# ProDoc___2025-04-08.net
KiCad netlist of a schematic drawn in EasyEDA Pro
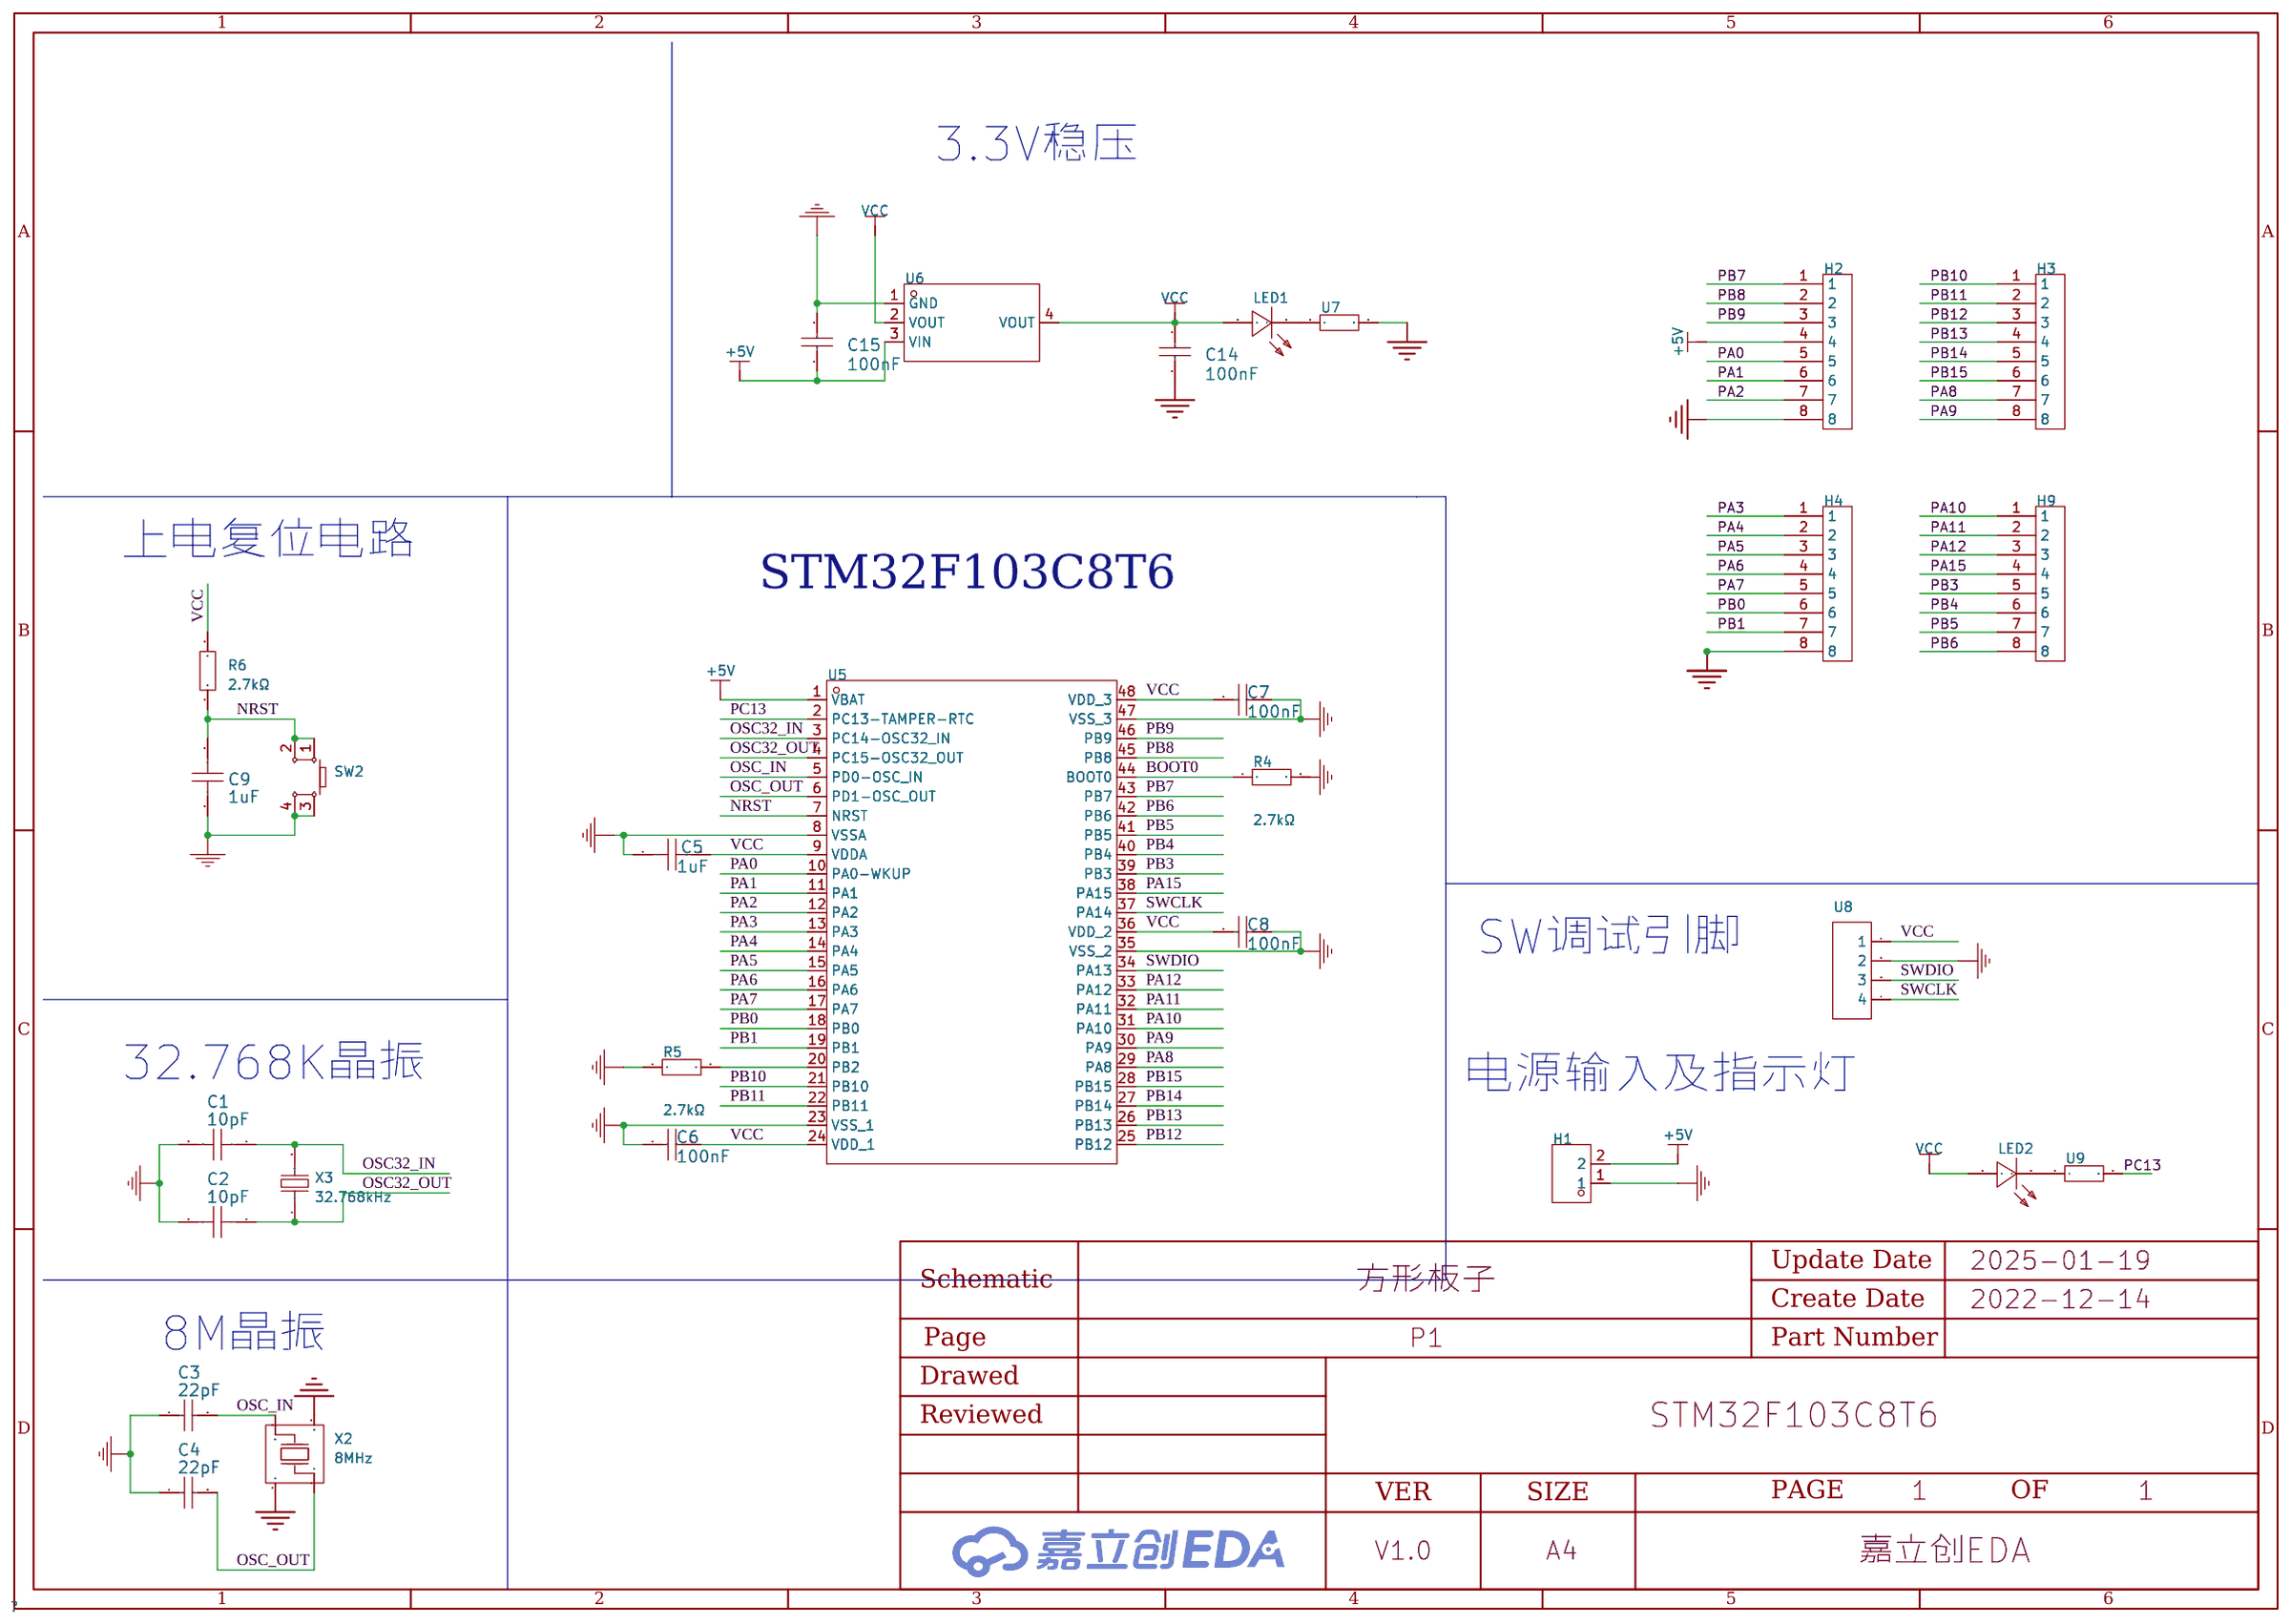
[diagram p0: schematic sheet]

(export (version "E")
  (design (tool "Eeschema 10.0.6"))
  (components
    (comp (ref "C1")
      (value "10pF")
      (footprint "easyedapro:C0603")
      (fields
        (field (name "Manufacturer Part") "CL10C100JB81PNC")
        (field (name "Manufacturer") "Samsung Electro-Mechanics")
      )
      (libsource (lib "easyedapro") (part "10pF"))
    )
    (comp (ref "C2")
      (value "10pF")
      (footprint "easyedapro:C0603")
      (fields
        (field (name "Manufacturer Part") "CL10C100JB81PNC")
        (field (name "Manufacturer") "Samsung Electro-Mechanics")
      )
      (libsource (lib "easyedapro") (part "10pF"))
    )
    (comp (ref "C3")
      (value "22pF")
      (footprint "easyedapro:C0603")
      (fields (field (name "Manufacturer Part") "CL10C220JB8NNNC") (field (name "Manufacturer") "SAMSUNG"))
      (libsource (lib "easyedapro") (part "22pF"))
    )
    (comp (ref "C4")
      (value "22pF")
      (footprint "easyedapro:C0603")
      (fields (field (name "Manufacturer Part") "CL10C220JB8NNNC") (field (name "Manufacturer") "SAMSUNG"))
      (libsource (lib "easyedapro") (part "22pF"))
    )
    (comp (ref "C5")
      (value "1uF")
      (footprint "easyedapro:C0603")
      (fields (field (name "Manufacturer Part") "C0603X5R105K250NT") (field (name "Manufacturer") "SANYEAR"))
      (libsource (lib "easyedapro") (part "1uF"))
    )
    (comp (ref "C6")
      (value "100nF")
      (footprint "easyedapro:C0603")
      (fields (field (name "Manufacturer Part") "0603B104K160") (field (name "Manufacturer") "WTC"))
      (libsource (lib "easyedapro") (part "100nF"))
    )
    (comp (ref "C7")
      (value "100nF")
      (footprint "easyedapro:C0603")
      (fields (field (name "Manufacturer Part") "0603B104K160") (field (name "Manufacturer") "WTC"))
      (libsource (lib "easyedapro") (part "100nF"))
    )
    (comp (ref "C8")
      (value "100nF")
      (footprint "easyedapro:C0603")
      (fields (field (name "Manufacturer Part") "0603B104K160") (field (name "Manufacturer") "WTC"))
      (libsource (lib "easyedapro") (part "100nF"))
    )
    (comp (ref "C9")
      (value "1uF")
      (footprint "easyedapro:C0603")
      (fields (field (name "Manufacturer Part") "C0603X5R105K250NT") (field (name "Manufacturer") "SANYEAR"))
      (libsource (lib "easyedapro") (part "1uF"))
    )
    (comp (ref "C14")
      (value "100nF")
      (footprint "easyedapro:C0603")
      (fields (field (name "Manufacturer Part") "0603B104K160") (field (name "Manufacturer") "WTC"))
      (libsource (lib "easyedapro") (part "100nF"))
    )
    (comp (ref "C15")
      (value "100nF")
      (footprint "easyedapro:C0603")
      (fields (field (name "Manufacturer Part") "0603B104K160") (field (name "Manufacturer") "WTC"))
      (libsource (lib "easyedapro") (part "100nF"))
    )
    (comp (ref "H1")
      (value "PZ254V-11-02P")
      (footprint "easyedapro:HDR-TH_2P-P2.54-V-M")
      (fields (field (name "Manufacturer") "XFCN(兴飞)"))
      (libsource (lib "easyedapro") (part "PZ254V-11-02P"))
    )
    (comp (ref "H2")
      (value "~")
      (footprint "easyedapro:排针8P-直针")
      (libsource (lib "easyedapro") (part "排针8P"))
    )
    (comp (ref "H3")
      (value "~")
      (footprint "easyedapro:排针8P-直针")
      (libsource (lib "easyedapro") (part "排针8P"))
    )
    (comp (ref "H4")
      (value "~")
      (footprint "easyedapro:排针8P-直针")
      (libsource (lib "easyedapro") (part "排针8P"))
    )
    (comp (ref "H9")
      (value "~")
      (footprint "easyedapro:排针8P-直针")
      (libsource (lib "easyedapro") (part "排针8P"))
    )
    (comp (ref "LED1")
      (value "KT-0603R")
      (footprint "easyedapro:LED0603-RD")
      (description "发光颜色:红色;功率:-;正向电流:-;主波长:-;二极管配置:-;透镜颜色:-;色温:-;发光角度:-;载带方式:-;工作温度:-40°C~+85°C;")
      (fields (field (name "Manufacturer") "KENTO"))
      (libsource (lib "easyedapro") (part "KT-0603R"))
    )
    (comp (ref "LED2")
      (value "KT-0603R")
      (footprint "easyedapro:LED0603-RD")
      (description "发光颜色:红色;功率:-;正向电流:-;主波长:-;二极管配置:-;透镜颜色:-;色温:-;发光角度:-;载带方式:-;工作温度:-40°C~+85°C;")
      (fields (field (name "Manufacturer") "KENTO"))
      (libsource (lib "easyedapro") (part "KT-0603R"))
    )
    (comp (ref "R4")
      (value "2.7kΩ")
      (footprint "easyedapro:R0603")
      (description "电阻类型:厚膜电阻;阻值:2.7kΩ;精度:±1%;功率:100mW;温度系数:±100ppm/°C;最大工作电压:75V;工作温度范围:-55°C~+155°C;")
      (fields
        (field (name "Manufacturer Part") "0603WAF2701T5E")
        (field (name "Manufacturer") "UNI-ROYAL(厚声)")
      )
      (libsource (lib "easyedapro") (part "电阻0603"))
    )
    (comp (ref "R5")
      (value "2.7kΩ")
      (footprint "easyedapro:R0603")
      (description "电阻类型:厚膜电阻;阻值:2.7kΩ;精度:±1%;功率:100mW;温度系数:±100ppm/°C;最大工作电压:75V;工作温度范围:-55°C~+155°C;")
      (fields
        (field (name "Manufacturer Part") "0603WAF2701T5E")
        (field (name "Manufacturer") "UNI-ROYAL(厚声)")
      )
      (libsource (lib "easyedapro") (part "电阻0603"))
    )
    (comp (ref "R6")
      (value "2.7kΩ")
      (footprint "easyedapro:R0603")
      (description "电阻类型:厚膜电阻;阻值:2.7kΩ;精度:±1%;功率:100mW;温度系数:±100ppm/°C;最大工作电压:75V;工作温度范围:-55°C~+155°C;")
      (fields
        (field (name "Manufacturer Part") "0603WAF2701T5E")
        (field (name "Manufacturer") "UNI-ROYAL(厚声)")
      )
      (libsource (lib "easyedapro") (part "电阻0603"))
    )
    (comp (ref "SW2")
      (value "~")
      (footprint "easyedapro:SW-TH_4P-L6.0-W6.0-P4.50-LS6.5")
      (libsource (lib "easyedapro") (part "轻触按键"))
    )
    (comp (ref "U5")
      (value "STM32F103C8T6")
      (footprint "easyedapro:LQFP-48_L7.0-W7.0-P0.50-LS9.0-BL")
      (description "CPU内核:ARM-M3;CPU最大主频:72MHz;应用领域:-;")
      (fields (field (name "Manufacturer") "ST(意法半导体)"))
      (libsource (lib "easyedapro") (part "STM32F103C8T6"))
    )
    (comp (ref "U6")
      (value "AMS1117-3.3")
      (footprint "easyedapro:SOT-223-3_L6.5-W3.4-P2.30-LS7.0-BR")
      (description "输出类型:固定;最大输入电压:-;输出电压:3.3V;最大输出电流:1A;电源纹波抑制比(PSRR):72dB@(120Hz);输出极性:正极;")
      (fields (field (name "Manufacturer") "AMS"))
      (libsource (lib "easyedapro") (part "AMS1117-3.3"))
    )
    (comp (ref "U7")
      (value "贴片电阻_0603_100K_±1%_1/10W")
      (footprint "easyedapro:R0603")
      (libsource (lib "easyedapro") (part "贴片电阻_0603_100K_±1%_1/10W"))
    )
    (comp (ref "U8")
      (value "~")
      (footprint "easyedapro:排针/排母4p")
      (libsource (lib "easyedapro") (part "排针4p"))
    )
    (comp (ref "U9")
      (value "贴片电阻_0603_100K_±1%_1/10W")
      (footprint "easyedapro:R0603")
      (libsource (lib "easyedapro") (part "贴片电阻_0603_100K_±1%_1/10W"))
    )
    (comp (ref "X2")
      (value "8MHz")
      (footprint "easyedapro:CRYSTAL-SMD_4P-L3.2-W2.5-BL")
      (description "晶振类型:贴片晶振;频率:8MHz;常温频差:±10ppm;负载电容:10pF;频率稳定度(全温):±15ppm;")
      (fields (field (name "Manufacturer Part") "TAXM8M4RDBCCT2T") (field (name "Manufacturer") "YJX(雅晶鑫)"))
      (libsource (lib "easyedapro") (part "TAXM8M4RDBCCT2T"))
    )
    (comp (ref "X3")
      (value "32.768kHz")
      (footprint "easyedapro:FC-135R_L3.2-W1.5")
      (description "晶振类型:贴片晶振;频率:32.768kHz;常温频差:±20ppm;负载电容:12.5pF;")
      (fields (field (name "Manufacturer Part") "Q13FC13500004") (field (name "Manufacturer") "EPSON(爱普生)"))
      (libsource (lib "easyedapro") (part "Q13FC1350000400"))
    )
  )
  (nets
    (net (code "1") (name "+5V") (class "Default")
      (node (ref "C15") (pin "2") (pinfunction "2_2") (pintype "input"))
      (node (ref "H1") (pin "2") (pinfunction "2_2") (pintype "unspecified"))
      (node (ref "H2") (pin "4") (pinfunction "4_4") (pintype "input"))
      (node (ref "U5") (pin "1") (pinfunction "VBAT_1") (pintype "unspecified"))
      (node (ref "U6") (pin "3") (pinfunction "VIN_3") (pintype "unspecified"))
    )
    (net (code "2") (name "/BOOT0") (class "Default")
      (node (ref "R4") (pin "1") (pinfunction "1_1") (pintype "input"))
      (node (ref "U5") (pin "44") (pinfunction "BOOT0_44") (pintype "unspecified"))
    )
    (net (code "3") (name "/NRST") (class "Default")
      (node (ref "C9") (pin "2") (pinfunction "2_2") (pintype "input"))
      (node (ref "R6") (pin "1") (pinfunction "1_1") (pintype "input"))
      (node (ref "SW2") (pin "1") (pinfunction "1_1") (pintype "input"))
      (node (ref "SW2") (pin "2") (pinfunction "2_2") (pintype "input"))
      (node (ref "U5") (pin "7") (pinfunction "NRST_7") (pintype "unspecified"))
    )
    (net (code "4") (name "/OSC32_IN") (class "Default")
      (node (ref "C1") (pin "1") (pinfunction "1_1") (pintype "input"))
      (node (ref "U5") (pin "3") (pinfunction "PC14-OSC32_IN_3") (pintype "unspecified"))
      (node (ref "X3") (pin "2") (pinfunction "2_2") (pintype "unspecified"))
    )
    (net (code "5") (name "/OSC32_OUT") (class "Default")
      (node (ref "C2") (pin "1") (pinfunction "1_1") (pintype "input"))
      (node (ref "U5") (pin "4") (pinfunction "PC15-OSC32_OUT_4") (pintype "unspecified"))
      (node (ref "X3") (pin "1") (pinfunction "1_1") (pintype "unspecified"))
    )
    (net (code "6") (name "/OSC_IN") (class "Default")
      (node (ref "C3") (pin "2") (pinfunction "2_2") (pintype "input"))
      (node (ref "U5") (pin "5") (pinfunction "PD0-OSC_IN_5") (pintype "unspecified"))
      (node (ref "X2") (pin "3") (pinfunction "3_3") (pintype "input"))
    )
    (net (code "7") (name "/OSC_OUT") (class "Default")
      (node (ref "C4") (pin "2") (pinfunction "2_2") (pintype "input"))
      (node (ref "U5") (pin "6") (pinfunction "PD1-OSC_OUT_6") (pintype "unspecified"))
      (node (ref "X2") (pin "1") (pinfunction "1_1") (pintype "input"))
    )
    (net (code "8") (name "/PA0") (class "Default")
      (node (ref "H2") (pin "5") (pinfunction "5_5") (pintype "input"))
      (node (ref "U5") (pin "10") (pinfunction "PA0-WKUP_10") (pintype "unspecified"))
    )
    (net (code "9") (name "/PA1") (class "Default")
      (node (ref "H2") (pin "6") (pinfunction "6_6") (pintype "input"))
      (node (ref "U5") (pin "11") (pinfunction "PA1_11") (pintype "unspecified"))
    )
    (net (code "10") (name "/PA2") (class "Default")
      (node (ref "H2") (pin "7") (pinfunction "7_7") (pintype "input"))
      (node (ref "U5") (pin "12") (pinfunction "PA2_12") (pintype "unspecified"))
    )
    (net (code "11") (name "/PA3") (class "Default")
      (node (ref "H4") (pin "1") (pinfunction "1_1") (pintype "input"))
      (node (ref "U5") (pin "13") (pinfunction "PA3_13") (pintype "unspecified"))
    )
    (net (code "12") (name "/PA4") (class "Default")
      (node (ref "H4") (pin "2") (pinfunction "2_2") (pintype "input"))
      (node (ref "U5") (pin "14") (pinfunction "PA4_14") (pintype "unspecified"))
    )
    (net (code "13") (name "/PA5") (class "Default")
      (node (ref "H4") (pin "3") (pinfunction "3_3") (pintype "input"))
      (node (ref "U5") (pin "15") (pinfunction "PA5_15") (pintype "unspecified"))
    )
    (net (code "14") (name "/PA6") (class "Default")
      (node (ref "H4") (pin "4") (pinfunction "4_4") (pintype "input"))
      (node (ref "U5") (pin "16") (pinfunction "PA6_16") (pintype "unspecified"))
    )
    (net (code "15") (name "/PA7") (class "Default")
      (node (ref "H4") (pin "5") (pinfunction "5_5") (pintype "input"))
      (node (ref "U5") (pin "17") (pinfunction "PA7_17") (pintype "unspecified"))
    )
    (net (code "16") (name "/PA8") (class "Default")
      (node (ref "H3") (pin "7") (pinfunction "7_7") (pintype "input"))
      (node (ref "U5") (pin "29") (pinfunction "PA8_29") (pintype "unspecified"))
    )
    (net (code "17") (name "/PA9") (class "Default")
      (node (ref "H3") (pin "8") (pinfunction "8_8") (pintype "input"))
      (node (ref "U5") (pin "30") (pinfunction "PA9_30") (pintype "unspecified"))
    )
    (net (code "18") (name "/PA10") (class "Default")
      (node (ref "H9") (pin "1") (pinfunction "1_1") (pintype "input"))
      (node (ref "U5") (pin "31") (pinfunction "PA10_31") (pintype "unspecified"))
    )
    (net (code "19") (name "/PA11") (class "Default")
      (node (ref "H9") (pin "2") (pinfunction "2_2") (pintype "input"))
      (node (ref "U5") (pin "32") (pinfunction "PA11_32") (pintype "unspecified"))
    )
    (net (code "20") (name "/PA12") (class "Default")
      (node (ref "H9") (pin "3") (pinfunction "3_3") (pintype "input"))
      (node (ref "U5") (pin "33") (pinfunction "PA12_33") (pintype "unspecified"))
    )
    (net (code "21") (name "/PA15") (class "Default")
      (node (ref "H9") (pin "4") (pinfunction "4_4") (pintype "input"))
      (node (ref "U5") (pin "38") (pinfunction "PA15_38") (pintype "unspecified"))
    )
    (net (code "22") (name "/PB0") (class "Default")
      (node (ref "H4") (pin "6") (pinfunction "6_6") (pintype "input"))
      (node (ref "U5") (pin "18") (pinfunction "PB0_18") (pintype "unspecified"))
    )
    (net (code "23") (name "/PB1") (class "Default")
      (node (ref "H4") (pin "7") (pinfunction "7_7") (pintype "input"))
      (node (ref "U5") (pin "19") (pinfunction "PB1_19") (pintype "unspecified"))
    )
    (net (code "24") (name "/PB3") (class "Default")
      (node (ref "H9") (pin "5") (pinfunction "5_5") (pintype "input"))
      (node (ref "U5") (pin "39") (pinfunction "PB3_39") (pintype "unspecified"))
    )
    (net (code "25") (name "/PB4") (class "Default")
      (node (ref "H9") (pin "6") (pinfunction "6_6") (pintype "input"))
      (node (ref "U5") (pin "40") (pinfunction "PB4_40") (pintype "unspecified"))
    )
    (net (code "26") (name "/PB5") (class "Default")
      (node (ref "H9") (pin "7") (pinfunction "7_7") (pintype "input"))
      (node (ref "U5") (pin "41") (pinfunction "PB5_41") (pintype "unspecified"))
    )
    (net (code "27") (name "/PB6") (class "Default")
      (node (ref "H9") (pin "8") (pinfunction "8_8") (pintype "input"))
      (node (ref "U5") (pin "42") (pinfunction "PB6_42") (pintype "unspecified"))
    )
    (net (code "28") (name "/PB7") (class "Default")
      (node (ref "H2") (pin "1") (pinfunction "1_1") (pintype "input"))
      (node (ref "U5") (pin "43") (pinfunction "PB7_43") (pintype "unspecified"))
    )
    (net (code "29") (name "/PB8") (class "Default")
      (node (ref "H2") (pin "2") (pinfunction "2_2") (pintype "input"))
      (node (ref "U5") (pin "45") (pinfunction "PB8_45") (pintype "unspecified"))
    )
    (net (code "30") (name "/PB9") (class "Default")
      (node (ref "H2") (pin "3") (pinfunction "3_3") (pintype "input"))
      (node (ref "U5") (pin "46") (pinfunction "PB9_46") (pintype "unspecified"))
    )
    (net (code "31") (name "/PB10") (class "Default")
      (node (ref "H3") (pin "1") (pinfunction "1_1") (pintype "input"))
      (node (ref "U5") (pin "21") (pinfunction "PB10_21") (pintype "unspecified"))
    )
    (net (code "32") (name "/PB11") (class "Default")
      (node (ref "H3") (pin "2") (pinfunction "2_2") (pintype "input"))
      (node (ref "U5") (pin "22") (pinfunction "PB11_22") (pintype "unspecified"))
    )
    (net (code "33") (name "/PB12") (class "Default")
      (node (ref "H3") (pin "3") (pinfunction "3_3") (pintype "input"))
      (node (ref "U5") (pin "25") (pinfunction "PB12_25") (pintype "unspecified"))
    )
    (net (code "34") (name "/PB13") (class "Default")
      (node (ref "H3") (pin "4") (pinfunction "4_4") (pintype "input"))
      (node (ref "U5") (pin "26") (pinfunction "PB13_26") (pintype "unspecified"))
    )
    (net (code "35") (name "/PB14") (class "Default")
      (node (ref "H3") (pin "5") (pinfunction "5_5") (pintype "input"))
      (node (ref "U5") (pin "27") (pinfunction "PB14_27") (pintype "unspecified"))
    )
    (net (code "36") (name "/PB15") (class "Default")
      (node (ref "H3") (pin "6") (pinfunction "6_6") (pintype "input"))
      (node (ref "U5") (pin "28") (pinfunction "PB15_28") (pintype "unspecified"))
    )
    (net (code "37") (name "/PC13") (class "Default")
      (node (ref "U5") (pin "2") (pinfunction "PC13-TAMPER-RTC_2") (pintype "unspecified"))
      (node (ref "U9") (pin "2") (pinfunction "2_2") (pintype "unspecified"))
    )
    (net (code "38") (name "/SWCLK") (class "Default")
      (node (ref "U5") (pin "37") (pinfunction "PA14_37") (pintype "unspecified"))
      (node (ref "U8") (pin "4") (pinfunction "4_4") (pintype "input"))
    )
    (net (code "39") (name "/SWDIO") (class "Default")
      (node (ref "U5") (pin "34") (pinfunction "PA13_34") (pintype "unspecified"))
      (node (ref "U8") (pin "3") (pinfunction "3_3") (pintype "input"))
    )
    (net (code "40") (name "GND") (class "Default")
      (node (ref "C1") (pin "2") (pinfunction "2_2") (pintype "input"))
      (node (ref "C14") (pin "2") (pinfunction "2_2") (pintype "input"))
      (node (ref "C15") (pin "1") (pinfunction "1_1") (pintype "input"))
      (node (ref "C2") (pin "2") (pinfunction "2_2") (pintype "input"))
      (node (ref "C3") (pin "1") (pinfunction "1_1") (pintype "input"))
      (node (ref "C4") (pin "1") (pinfunction "1_1") (pintype "input"))
      (node (ref "C5") (pin "1") (pinfunction "1_1") (pintype "input"))
      (node (ref "C6") (pin "1") (pinfunction "1_1") (pintype "input"))
      (node (ref "C7") (pin "2") (pinfunction "2_2") (pintype "input"))
      (node (ref "C8") (pin "2") (pinfunction "2_2") (pintype "input"))
      (node (ref "C9") (pin "1") (pinfunction "1_1") (pintype "input"))
      (node (ref "H1") (pin "1") (pinfunction "1_1") (pintype "unspecified"))
      (node (ref "H2") (pin "8") (pinfunction "8_8") (pintype "input"))
      (node (ref "H4") (pin "8") (pinfunction "8_8") (pintype "input"))
      (node (ref "R4") (pin "2") (pinfunction "2_2") (pintype "input"))
      (node (ref "R5") (pin "1") (pinfunction "1_1") (pintype "input"))
      (node (ref "SW2") (pin "3") (pinfunction "3_3") (pintype "input"))
      (node (ref "SW2") (pin "4") (pinfunction "4_4") (pintype "input"))
      (node (ref "U5") (pin "23") (pinfunction "VSS_1_23") (pintype "unspecified"))
      (node (ref "U5") (pin "35") (pinfunction "VSS_2_35") (pintype "unspecified"))
      (node (ref "U5") (pin "47") (pinfunction "VSS_3_47") (pintype "unspecified"))
      (node (ref "U5") (pin "8") (pinfunction "VSSA_8") (pintype "unspecified"))
      (node (ref "U6") (pin "1") (pinfunction "GND_1") (pintype "unspecified"))
      (node (ref "U7") (pin "2") (pinfunction "2_2") (pintype "unspecified"))
      (node (ref "U8") (pin "2") (pinfunction "2_2") (pintype "input"))
      (node (ref "X2") (pin "2") (pinfunction "2_2") (pintype "input"))
      (node (ref "X2") (pin "4") (pinfunction "4_4") (pintype "input"))
    )
    (net (code "41") (name "Net-(LED1-K)") (class "Default")
      (node (ref "LED1") (pin "1") (pinfunction "K_1") (pintype "unspecified"))
      (node (ref "U7") (pin "1") (pinfunction "1_1") (pintype "unspecified"))
    )
    (net (code "42") (name "Net-(LED2-K)") (class "Default")
      (node (ref "LED2") (pin "1") (pinfunction "K_1") (pintype "unspecified"))
      (node (ref "U9") (pin "1") (pinfunction "1_1") (pintype "unspecified"))
    )
    (net (code "43") (name "Net-(U5-PB2)") (class "Default")
      (node (ref "R5") (pin "2") (pinfunction "2_2") (pintype "input"))
      (node (ref "U5") (pin "20") (pinfunction "PB2_20") (pintype "unspecified"))
    )
    (net (code "44") (name "VCC") (class "Default")
      (node (ref "C14") (pin "1") (pinfunction "1_1") (pintype "input"))
      (node (ref "C5") (pin "2") (pinfunction "2_2") (pintype "input"))
      (node (ref "C6") (pin "2") (pinfunction "2_2") (pintype "input"))
      (node (ref "C7") (pin "1") (pinfunction "1_1") (pintype "input"))
      (node (ref "C8") (pin "1") (pinfunction "1_1") (pintype "input"))
      (node (ref "LED1") (pin "2") (pinfunction "A_2") (pintype "unspecified"))
      (node (ref "LED2") (pin "2") (pinfunction "A_2") (pintype "unspecified"))
      (node (ref "R6") (pin "2") (pinfunction "2_2") (pintype "input"))
      (node (ref "U5") (pin "24") (pinfunction "VDD_1_24") (pintype "unspecified"))
      (node (ref "U5") (pin "36") (pinfunction "VDD_2_36") (pintype "unspecified"))
      (node (ref "U5") (pin "48") (pinfunction "VDD_3_48") (pintype "unspecified"))
      (node (ref "U5") (pin "9") (pinfunction "VDDA_9") (pintype "unspecified"))
      (node (ref "U6") (pin "2") (pinfunction "VOUT_2") (pintype "unspecified"))
      (node (ref "U6") (pin "4") (pinfunction "VOUT_4") (pintype "unspecified"))
      (node (ref "U8") (pin "1") (pinfunction "1_1") (pintype "input"))
    )
  )
)
